# ATMEGA328P-AU_Board.net
KiCad netlist of a schematic drawn in EAGLE
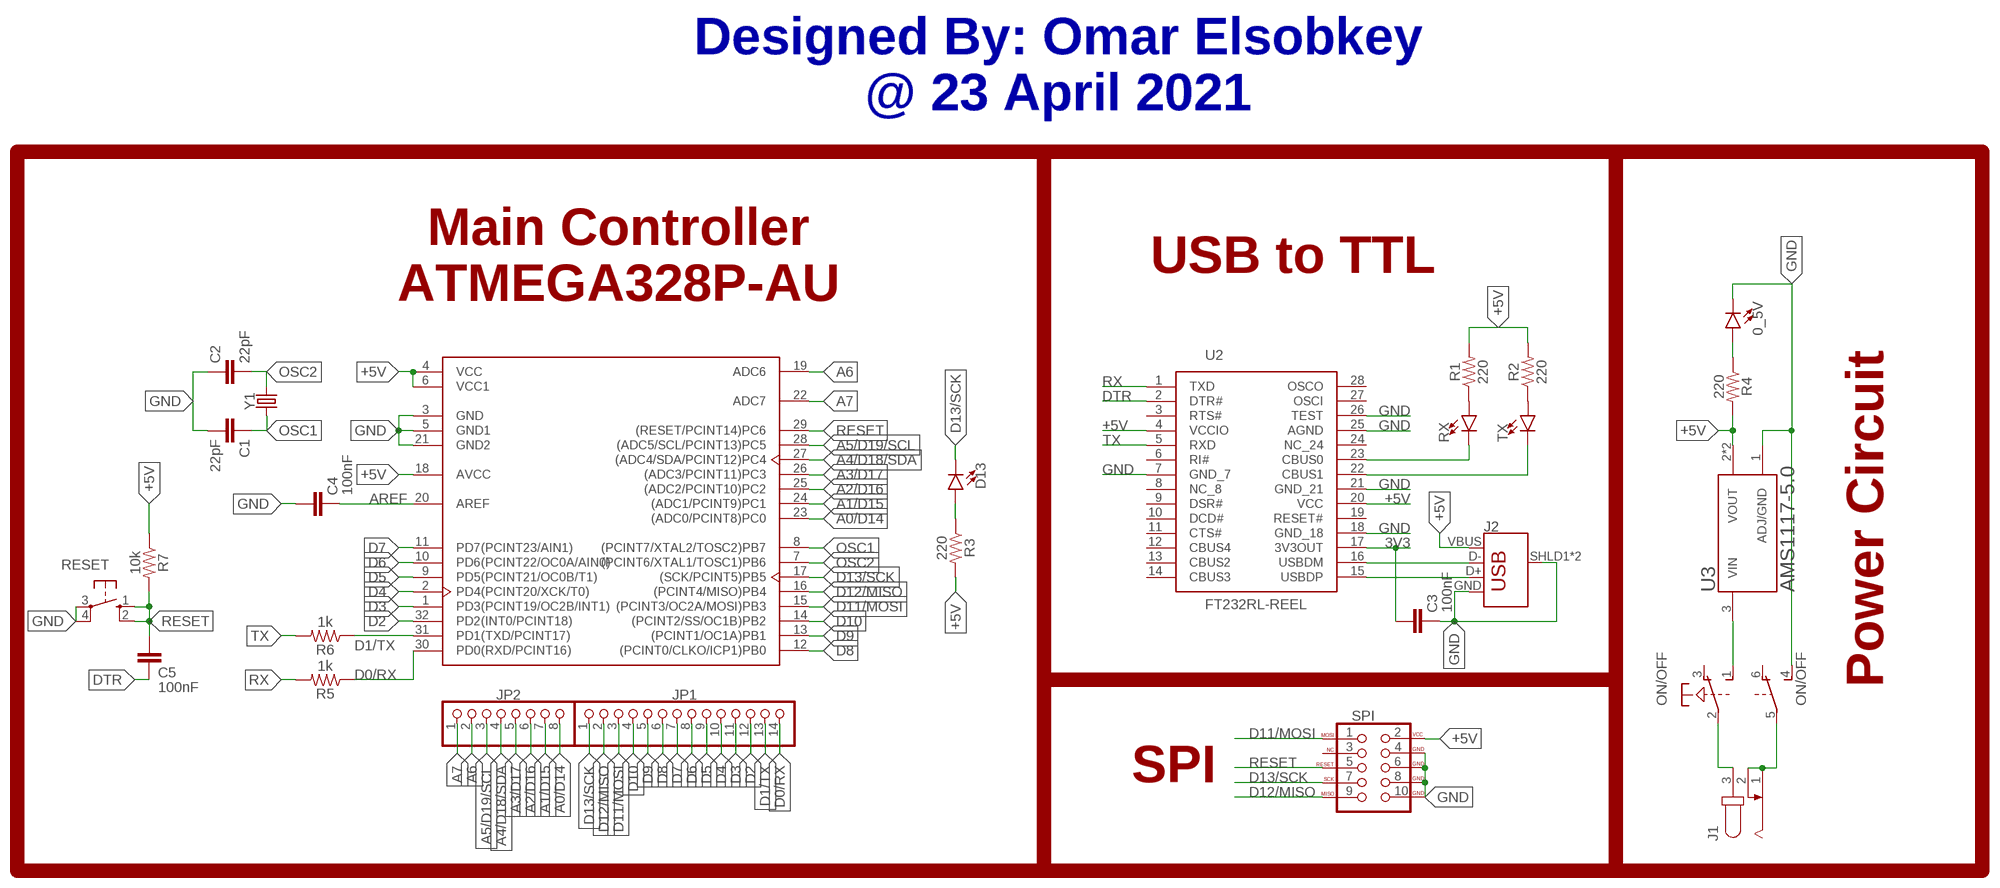
[diagram p0: schematic, sheet 1]

(export (version "E")
  (design (tool "Eeschema 10.0.6"))
  (components
    (comp (ref "0_5V")
      (value "LED3MM")
      (footprint "eagle-import:LED_3MM")
      (libsource (lib "eagle-import") (part "LED3MM"))
    )
    (comp (ref "C1")
      (value "22pF")
      (footprint "eagle-import:CAP-PTH-2.54")
      (libsource (lib "eagle-import") (part "22PF-PTH-2.54MM-200V-5%"))
    )
    (comp (ref "C2")
      (value "22pF")
      (footprint "eagle-import:CAP-PTH-2.54")
      (libsource (lib "eagle-import") (part "22PF-PTH-2.54MM-200V-5%"))
    )
    (comp (ref "C3")
      (value "100nF")
      (footprint "eagle-import:CAP-PTH-2.54")
      (libsource (lib "eagle-import") (part "22PF-PTH-2.54MM-200V-5%"))
    )
    (comp (ref "C4")
      (value "100nF")
      (footprint "eagle-import:CAP-PTH-2.54")
      (libsource (lib "eagle-import") (part "22PF-PTH-2.54MM-200V-5%"))
    )
    (comp (ref "C5")
      (value "100nF")
      (footprint "eagle-import:CAP-PTH-2.54")
      (libsource (lib "eagle-import") (part "22PF-PTH-2.54MM-200V-5%"))
    )
    (comp (ref "D13")
      (value "LED3MM")
      (footprint "eagle-import:LED_3MM")
      (libsource (lib "eagle-import") (part "LED3MM"))
    )
    (comp (ref "J1")
      (value "JACK-PLUG0")
      (footprint "eagle-import:SPC4077")
      (libsource (lib "eagle-import") (part "JACK-PLUG0"))
    )
    (comp (ref "J2")
      (value "USB_B_PTH")
      (footprint "eagle-import:USB-B-PTH")
      (libsource (lib "eagle-import") (part "USB_B_PTH"))
    )
    (comp (ref "JP1")
      (value "PINHD-1X14")
      (footprint "eagle-import:1X14")
      (libsource (lib "eagle-import") (part "PINHD-1X14"))
    )
    (comp (ref "JP2")
      (value "PINHD-1X8")
      (footprint "eagle-import:1X08")
      (libsource (lib "eagle-import") (part "PINHD-1X8"))
    )
    (comp (ref "ON/OFF")
      (value "PVA2R")
      (footprint "eagle-import:PVA2R")
      (libsource (lib "eagle-import") (part "PVA2R"))
    )
    (comp (ref "R1")
      (value "220")
      (footprint "eagle-import:1206")
      (libsource (lib "eagle-import") (part "RESISTOR1206"))
    )
    (comp (ref "R2")
      (value "220")
      (footprint "eagle-import:1206")
      (libsource (lib "eagle-import") (part "RESISTOR1206"))
    )
    (comp (ref "R3")
      (value "220")
      (footprint "eagle-import:1206")
      (libsource (lib "eagle-import") (part "RESISTOR1206"))
    )
    (comp (ref "R4")
      (value "220")
      (footprint "eagle-import:1206")
      (libsource (lib "eagle-import") (part "RESISTOR1206"))
    )
    (comp (ref "R5")
      (value "1k")
      (footprint "eagle-import:1206")
      (libsource (lib "eagle-import") (part "RESISTOR1206"))
    )
    (comp (ref "R6")
      (value "1k")
      (footprint "eagle-import:1206")
      (libsource (lib "eagle-import") (part "RESISTOR1206"))
    )
    (comp (ref "R7")
      (value "10k")
      (footprint "eagle-import:1206")
      (libsource (lib "eagle-import") (part "RESISTOR1206"))
    )
    (comp (ref "RESET")
      (value "10-XX")
      (footprint "eagle-import:B3F-10XX")
      (fields (field (name "MPN") "B3F-1000"))
      (libsource (lib "eagle-import") (part "10-XX"))
    )
    (comp (ref "RX")
      (value "LED3MM")
      (footprint "eagle-import:LED_3MM")
      (libsource (lib "eagle-import") (part "LED3MM"))
    )
    (comp (ref "SPI")
      (value "AVR_SPI_PROG_5X2LOCK")
      (footprint "eagle-import:2X5-SHROUDED_LOCK")
      (libsource (lib "eagle-import") (part "AVR_SPI_PROG_5X2LOCK"))
    )
    (comp (ref "TX")
      (value "LED3MM")
      (footprint "eagle-import:LED_3MM")
      (libsource (lib "eagle-import") (part "LED3MM"))
    )
    (comp (ref "U1")
      (value "ATMEGA328P-AU")
      (footprint "eagle-import:TQFP-32")
      (fields
        (field (name "DIGIKEY_PART_NUMBER") "ATMEGA328P-AU-ND")
        (field (name "MANUFACTURER") "Microchip Technology")
        (field (name "CREATED_BY") "PCBLayout.com")
      )
      (libsource (lib "eagle-import") (part "ATMEGA328P-AU"))
    )
    (comp (ref "U2")
      (value "FT232RL-REEL")
      (footprint "eagle-import:SSOP-28")
      (fields
        (field (name "DIGI-KEYPARTNUMBER") "768-1007-1-ND")
        (field (name "MANUFACTURER") "FTDI, Future Technology Devices International Ltd")
        (field (name "CREATED_BY") "PCBLayout.com")
      )
      (libsource (lib "eagle-import") (part "FT232RL-REEL"))
    )
    (comp (ref "U3")
      (value "AMS1117-5.0")
      (footprint "eagle-import:AMS1117-5.0")
      (fields (field (name "MF") "Advanced Monolithic Systems"))
      (libsource (lib "eagle-import") (part "AMS1117-5.0"))
    )
    (comp (ref "Y1")
      (value "CRYSTALPTH-HC49UV")
      (footprint "eagle-import:HC49U")
      (libsource (lib "eagle-import") (part "CRYSTALPTH-HC49UV"))
    )
  )
  (nets
    (net (code "1") (name "+5V") (class "Default")
      (node (ref "J2") (pin "VBUS") (pinfunction "VBUS_VBUS") (pintype "power_in"))
      (node (ref "R1") (pin "2") (pinfunction "2_2") (pintype "passive"))
      (node (ref "R2") (pin "2") (pinfunction "2_2") (pintype "passive"))
      (node (ref "R3") (pin "2") (pinfunction "2_2") (pintype "passive"))
      (node (ref "R4") (pin "2") (pinfunction "2_2") (pintype "passive"))
      (node (ref "R7") (pin "1") (pinfunction "1_1") (pintype "passive"))
      (node (ref "SPI") (pin "2") (pinfunction "VCC_2") (pintype "power_in"))
      (node (ref "U1") (pin "18") (pinfunction "AVCC_18") (pintype "power_in"))
      (node (ref "U1") (pin "4") (pinfunction "VCC_4") (pintype "power_in"))
      (node (ref "U1") (pin "6") (pinfunction "VCC1_6") (pintype "power_in"))
      (node (ref "U2") (pin "20") (pinfunction "VCC_20") (pintype "power_in"))
      (node (ref "U2") (pin "4") (pinfunction "VCCIO_4") (pintype "power_in"))
      (node (ref "U3") (pin "2") (pinfunction "VOUT_2") (pintype "output"))
      (node (ref "U3") (pin "4") (pinfunction "VOUT_4") (pintype "output"))
    )
    (net (code "2") (name "/3V3") (class "Default")
      (node (ref "C3") (pin "1") (pinfunction "1_1") (pintype "passive"))
      (node (ref "U2") (pin "17") (pinfunction "3V3OUT_17") (pintype "output"))
    )
    (net (code "3") (name "/AREF") (class "Default")
      (node (ref "C4") (pin "2") (pinfunction "2_2") (pintype "passive"))
      (node (ref "U1") (pin "20") (pinfunction "AREF_20") (pintype "power_in"))
    )
    (net (code "4") (name "A0{slash}D14") (class "Default")
      (node (ref "JP2") (pin "8") (pinfunction "8_8") (pintype "passive"))
      (node (ref "U1") (pin "23") (pinfunction "(ADC0/PCINT8)PC0_23") (pintype "bidirectional"))
    )
    (net (code "5") (name "A1{slash}D15") (class "Default")
      (node (ref "JP2") (pin "7") (pinfunction "7_7") (pintype "passive"))
      (node (ref "U1") (pin "24") (pinfunction "(ADC1/PCINT9)PC1_24") (pintype "bidirectional"))
    )
    (net (code "6") (name "A2{slash}D16") (class "Default")
      (node (ref "JP2") (pin "6") (pinfunction "6_6") (pintype "passive"))
      (node (ref "U1") (pin "25") (pinfunction "(ADC2/PCINT10)PC2_25") (pintype "bidirectional"))
    )
    (net (code "7") (name "A3{slash}D17") (class "Default")
      (node (ref "JP2") (pin "5") (pinfunction "5_5") (pintype "passive"))
      (node (ref "U1") (pin "26") (pinfunction "(ADC3/PCINT11)PC3_26") (pintype "bidirectional"))
    )
    (net (code "8") (name "A4{slash}D18{slash}SDA") (class "Default")
      (node (ref "JP2") (pin "4") (pinfunction "4_4") (pintype "passive"))
      (node (ref "U1") (pin "27") (pinfunction "(ADC4/SDA/PCINT12)PC4_27") (pintype "bidirectional"))
    )
    (net (code "9") (name "A5{slash}D19{slash}SCL") (class "Default")
      (node (ref "JP2") (pin "3") (pinfunction "3_3") (pintype "passive"))
      (node (ref "U1") (pin "28") (pinfunction "(ADC5/SCL/PCINT13)PC5_28") (pintype "bidirectional"))
    )
    (net (code "10") (name "A6") (class "Default")
      (node (ref "JP2") (pin "2") (pinfunction "2_2") (pintype "passive"))
      (node (ref "U1") (pin "19") (pinfunction "ADC6_19") (pintype "input"))
    )
    (net (code "11") (name "A7") (class "Default")
      (node (ref "JP2") (pin "1") (pinfunction "1_1") (pintype "passive"))
      (node (ref "U1") (pin "22") (pinfunction "ADC7_22") (pintype "input"))
    )
    (net (code "12") (name "D0{slash}RX") (class "Default")
      (node (ref "JP1") (pin "14") (pinfunction "14_14") (pintype "passive"))
      (node (ref "R5") (pin "1") (pinfunction "1_1") (pintype "passive"))
      (node (ref "U1") (pin "30") (pinfunction "PD0(RXD/PCINT16)_30") (pintype "bidirectional"))
    )
    (net (code "13") (name "D1{slash}TX") (class "Default")
      (node (ref "JP1") (pin "13") (pinfunction "13_13") (pintype "passive"))
      (node (ref "R6") (pin "1") (pinfunction "1_1") (pintype "passive"))
      (node (ref "U1") (pin "31") (pinfunction "PD1(TXD/PCINT17)_31") (pintype "bidirectional"))
    )
    (net (code "14") (name "D2") (class "Default")
      (node (ref "JP1") (pin "12") (pinfunction "12_12") (pintype "passive"))
      (node (ref "U1") (pin "32") (pinfunction "PD2(INT0/PCINT18)_32") (pintype "bidirectional"))
    )
    (net (code "15") (name "D3") (class "Default")
      (node (ref "JP1") (pin "11") (pinfunction "11_11") (pintype "passive"))
      (node (ref "U1") (pin "1") (pinfunction "PD3(PCINT19/OC2B/INT1)_1") (pintype "bidirectional"))
    )
    (net (code "16") (name "D4") (class "Default")
      (node (ref "JP1") (pin "10") (pinfunction "10_10") (pintype "passive"))
      (node (ref "U1") (pin "2") (pinfunction "PD4(PCINT20/XCK/T0)_2") (pintype "bidirectional"))
    )
    (net (code "17") (name "D5") (class "Default")
      (node (ref "JP1") (pin "9") (pinfunction "9_9") (pintype "passive"))
      (node (ref "U1") (pin "9") (pinfunction "PD5(PCINT21/OC0B/T1)_9") (pintype "bidirectional"))
    )
    (net (code "18") (name "D6") (class "Default")
      (node (ref "JP1") (pin "8") (pinfunction "8_8") (pintype "passive"))
      (node (ref "U1") (pin "10") (pinfunction "PD6(PCINT22/OC0A/AIN0)_10") (pintype "bidirectional"))
    )
    (net (code "19") (name "D7") (class "Default")
      (node (ref "JP1") (pin "7") (pinfunction "7_7") (pintype "passive"))
      (node (ref "U1") (pin "11") (pinfunction "PD7(PCINT23/AIN1)_11") (pintype "bidirectional"))
    )
    (net (code "20") (name "D8") (class "Default")
      (node (ref "JP1") (pin "6") (pinfunction "6_6") (pintype "passive"))
      (node (ref "U1") (pin "12") (pinfunction "(PCINT0/CLKO/ICP1)PB0_12") (pintype "bidirectional"))
    )
    (net (code "21") (name "D9") (class "Default")
      (node (ref "JP1") (pin "5") (pinfunction "5_5") (pintype "passive"))
      (node (ref "U1") (pin "13") (pinfunction "(PCINT1/OC1A)PB1_13") (pintype "bidirectional"))
    )
    (net (code "22") (name "D10") (class "Default")
      (node (ref "JP1") (pin "4") (pinfunction "4_4") (pintype "passive"))
      (node (ref "U1") (pin "14") (pinfunction "(PCINT2/SS/OC1B)PB2_14") (pintype "bidirectional"))
    )
    (net (code "23") (name "D11{slash}MOSI") (class "Default")
      (node (ref "JP1") (pin "3") (pinfunction "3_3") (pintype "passive"))
      (node (ref "SPI") (pin "1") (pinfunction "MOSI_1") (pintype "passive"))
      (node (ref "U1") (pin "15") (pinfunction "(PCINT3/OC2A/MOSI)PB3_15") (pintype "bidirectional"))
    )
    (net (code "24") (name "D12{slash}MISO") (class "Default")
      (node (ref "JP1") (pin "2") (pinfunction "2_2") (pintype "passive"))
      (node (ref "SPI") (pin "9") (pinfunction "MISO_9") (pintype "passive"))
      (node (ref "U1") (pin "16") (pinfunction "(PCINT4/MISO)PB4_16") (pintype "bidirectional"))
    )
    (net (code "25") (name "D13{slash}SCK") (class "Default")
      (node (ref "D13") (pin "K") (pinfunction "C_K") (pintype "passive"))
      (node (ref "JP1") (pin "1") (pinfunction "1_1") (pintype "passive"))
      (node (ref "SPI") (pin "7") (pinfunction "SCK_7") (pintype "passive"))
      (node (ref "U1") (pin "17") (pinfunction "(SCK/PCINT5)PB5_17") (pintype "bidirectional"))
    )
    (net (code "26") (name "DTR") (class "Default")
      (node (ref "C5") (pin "2") (pinfunction "2_2") (pintype "passive"))
      (node (ref "U2") (pin "2") (pinfunction "DTR#_2") (pintype "output"))
    )
    (net (code "27") (name "GND") (class "Default")
      (node (ref "0_5V") (pin "K") (pinfunction "C_K") (pintype "passive"))
      (node (ref "C1") (pin "2") (pinfunction "2_2") (pintype "passive"))
      (node (ref "C2") (pin "1") (pinfunction "1_1") (pintype "passive"))
      (node (ref "C3") (pin "2") (pinfunction "2_2") (pintype "passive"))
      (node (ref "C4") (pin "1") (pinfunction "1_1") (pintype "passive"))
      (node (ref "J2") (pin "GND") (pinfunction "GND_GND") (pintype "power_in"))
      (node (ref "J2") (pin "SHLD1") (pinfunction "SHIELD_SHLD1") (pintype "bidirectional"))
      (node (ref "J2") (pin "SHLD2") (pinfunction "SHIELD_SHLD2") (pintype "bidirectional"))
      (node (ref "ON/OFF") (pin "4") (pinfunction "S_4") (pintype "passive"))
      (node (ref "RESET") (pin "3") (pinfunction "P_3") (pintype "passive"))
      (node (ref "RESET") (pin "4") (pinfunction "P1_4") (pintype "passive"))
      (node (ref "SPI") (pin "10") (pinfunction "GND_10") (pintype "power_in"))
      (node (ref "SPI") (pin "4") (pinfunction "GND_4") (pintype "power_in"))
      (node (ref "SPI") (pin "6") (pinfunction "GND_6") (pintype "power_in"))
      (node (ref "SPI") (pin "8") (pinfunction "GND_8") (pintype "power_in"))
      (node (ref "U1") (pin "21") (pinfunction "GND2_21") (pintype "power_in"))
      (node (ref "U1") (pin "3") (pinfunction "GND_3") (pintype "power_in"))
      (node (ref "U1") (pin "5") (pinfunction "GND1_5") (pintype "power_in"))
      (node (ref "U2") (pin "18") (pinfunction "GND_18_18") (pintype "power_in"))
      (node (ref "U2") (pin "21") (pinfunction "GND_21_21") (pintype "power_in"))
      (node (ref "U2") (pin "25") (pinfunction "AGND_25") (pintype "power_in"))
      (node (ref "U2") (pin "26") (pinfunction "TEST_26") (pintype "input"))
      (node (ref "U2") (pin "7") (pinfunction "GND_7_7") (pintype "power_in"))
      (node (ref "U3") (pin "1") (pinfunction "ADJ/GND_1") (pintype "power_in"))
    )
    (net (code "28") (name "Net-(0_5V-PadA)") (class "Default")
      (node (ref "0_5V") (pin "A") (pinfunction "A_A") (pintype "passive"))
      (node (ref "R4") (pin "1") (pinfunction "1_1") (pintype "passive"))
    )
    (net (code "29") (name "Net-(D13-PadA)") (class "Default")
      (node (ref "D13") (pin "A") (pinfunction "A_A") (pintype "passive"))
      (node (ref "R3") (pin "1") (pinfunction "1_1") (pintype "passive"))
    )
    (net (code "30") (name "Net-(ON/OFFA-P)") (class "Default")
      (node (ref "J1") (pin "3") (pinfunction "3_3") (pintype "passive"))
      (node (ref "ON/OFF") (pin "2") (pinfunction "P_2") (pintype "passive"))
    )
    (net (code "31") (name "Net-(ON/OFFA-S)") (class "Default")
      (node (ref "ON/OFF") (pin "1") (pinfunction "S_1") (pintype "passive"))
      (node (ref "U3") (pin "3") (pinfunction "VIN_3") (pintype "input"))
    )
    (net (code "32") (name "Net-(ON/OFFB-P)") (class "Default")
      (node (ref "J1") (pin "1") (pinfunction "1_1") (pintype "passive"))
      (node (ref "J1") (pin "2") (pinfunction "2_2") (pintype "passive"))
      (node (ref "ON/OFF") (pin "5") (pinfunction "P_5") (pintype "passive"))
    )
    (net (code "33") (name "Net-(R1-Pad1)") (class "Default")
      (node (ref "R1") (pin "1") (pinfunction "1_1") (pintype "passive"))
      (node (ref "RX") (pin "A") (pinfunction "A_A") (pintype "passive"))
    )
    (net (code "34") (name "Net-(R2-Pad1)") (class "Default")
      (node (ref "R2") (pin "1") (pinfunction "1_1") (pintype "passive"))
      (node (ref "TX") (pin "A") (pinfunction "A_A") (pintype "passive"))
    )
    (net (code "35") (name "Net-(RX-C)") (class "Default")
      (node (ref "RX") (pin "K") (pinfunction "C_K") (pintype "passive"))
      (node (ref "U2") (pin "23") (pinfunction "CBUS0_23") (pintype "bidirectional"))
    )
    (net (code "36") (name "Net-(TX-C)") (class "Default")
      (node (ref "TX") (pin "K") (pinfunction "C_K") (pintype "passive"))
      (node (ref "U2") (pin "22") (pinfunction "CBUS1_22") (pintype "bidirectional"))
    )
    (net (code "37") (name "Net-(U2-USBDM)") (class "Default")
      (node (ref "J2") (pin "D-") (pinfunction "D-_D-") (pintype "bidirectional"))
      (node (ref "U2") (pin "16") (pinfunction "USBDM_16") (pintype "bidirectional"))
    )
    (net (code "38") (name "Net-(U2-USBDP)") (class "Default")
      (node (ref "J2") (pin "D+") (pinfunction "D+_D+") (pintype "bidirectional"))
      (node (ref "U2") (pin "15") (pinfunction "USBDP_15") (pintype "bidirectional"))
    )
    (net (code "39") (name "OSC1") (class "Default")
      (node (ref "C1") (pin "1") (pinfunction "1_1") (pintype "passive"))
      (node (ref "U1") (pin "8") (pinfunction "(PCINT7/XTAL2/TOSC2)PB7_8") (pintype "bidirectional"))
      (node (ref "Y1") (pin "1") (pinfunction "1_1") (pintype "passive"))
    )
    (net (code "40") (name "OSC2") (class "Default")
      (node (ref "C2") (pin "2") (pinfunction "2_2") (pintype "passive"))
      (node (ref "U1") (pin "7") (pinfunction "(PCINT6/XTAL1/TOSC1)PB6_7") (pintype "bidirectional"))
      (node (ref "Y1") (pin "2") (pinfunction "2_2") (pintype "passive"))
    )
    (net (code "41") (name "RESET") (class "Default")
      (node (ref "C5") (pin "1") (pinfunction "1_1") (pintype "passive"))
      (node (ref "R7") (pin "2") (pinfunction "2_2") (pintype "passive"))
      (node (ref "RESET") (pin "1") (pinfunction "S_1") (pintype "passive"))
      (node (ref "RESET") (pin "2") (pinfunction "S1_2") (pintype "passive"))
      (node (ref "SPI") (pin "5") (pinfunction "RESET_5") (pintype "passive"))
      (node (ref "U1") (pin "29") (pinfunction "(RESET/PCINT14)PC6_29") (pintype "bidirectional"))
    )
    (net (code "42") (name "RX") (class "Default")
      (node (ref "R5") (pin "2") (pinfunction "2_2") (pintype "passive"))
      (node (ref "U2") (pin "1") (pinfunction "TXD_1") (pintype "output"))
    )
    (net (code "43") (name "TX") (class "Default")
      (node (ref "R6") (pin "2") (pinfunction "2_2") (pintype "passive"))
      (node (ref "U2") (pin "5") (pinfunction "RXD_5") (pintype "input"))
    )
    (net (code "44") (name "unconnected-(ON/OFFA-O-Pad3)") (class "Default")
      (node (ref "ON/OFF") (pin "3") (pinfunction "O_3") (pintype "passive"))
    )
    (net (code "45") (name "unconnected-(ON/OFFB-O-Pad6)") (class "Default")
      (node (ref "ON/OFF") (pin "6") (pinfunction "O_6") (pintype "passive"))
    )
    (net (code "46") (name "unconnected-(SPI-NC-Pad3)") (class "Default")
      (node (ref "SPI") (pin "3") (pinfunction "NC_3") (pintype "no_connect"))
    )
    (net (code "47") (name "unconnected-(U2-CBUS2-Pad13)") (class "Default")
      (node (ref "U2") (pin "13") (pinfunction "CBUS2_13") (pintype "bidirectional"))
    )
    (net (code "48") (name "unconnected-(U2-CBUS3-Pad14)") (class "Default")
      (node (ref "U2") (pin "14") (pinfunction "CBUS3_14") (pintype "bidirectional"))
    )
    (net (code "49") (name "unconnected-(U2-CBUS4-Pad12)") (class "Default")
      (node (ref "U2") (pin "12") (pinfunction "CBUS4_12") (pintype "bidirectional"))
    )
    (net (code "50") (name "unconnected-(U2-CTS#-Pad11)") (class "Default")
      (node (ref "U2") (pin "11") (pinfunction "CTS#_11") (pintype "input"))
    )
    (net (code "51") (name "unconnected-(U2-DCD#-Pad10)") (class "Default")
      (node (ref "U2") (pin "10") (pinfunction "DCD#_10") (pintype "input"))
    )
    (net (code "52") (name "unconnected-(U2-DSR#-Pad9)") (class "Default")
      (node (ref "U2") (pin "9") (pinfunction "DSR#_9") (pintype "input"))
    )
    (net (code "53") (name "unconnected-(U2-NC_8-Pad8)") (class "Default")
      (node (ref "U2") (pin "8") (pinfunction "NC_8_8") (pintype "no_connect"))
    )
    (net (code "54") (name "unconnected-(U2-NC_24-Pad24)") (class "Default")
      (node (ref "U2") (pin "24") (pinfunction "NC_24_24") (pintype "no_connect"))
    )
    (net (code "55") (name "unconnected-(U2-OSCI-Pad27)") (class "Default")
      (node (ref "U2") (pin "27") (pinfunction "OSCI_27") (pintype "input"))
    )
    (net (code "56") (name "unconnected-(U2-OSCO-Pad28)") (class "Default")
      (node (ref "U2") (pin "28") (pinfunction "OSCO_28") (pintype "output"))
    )
    (net (code "57") (name "unconnected-(U2-RESET#-Pad19)") (class "Default")
      (node (ref "U2") (pin "19") (pinfunction "RESET#_19") (pintype "input"))
    )
    (net (code "58") (name "unconnected-(U2-RI#-Pad6)") (class "Default")
      (node (ref "U2") (pin "6") (pinfunction "RI#_6") (pintype "input"))
    )
    (net (code "59") (name "unconnected-(U2-RTS#-Pad3)") (class "Default")
      (node (ref "U2") (pin "3") (pinfunction "RTS#_3") (pintype "output"))
    )
  )
)
